# HAE_Sensors.net
KiCad netlist of a schematic drawn in Altium Designer
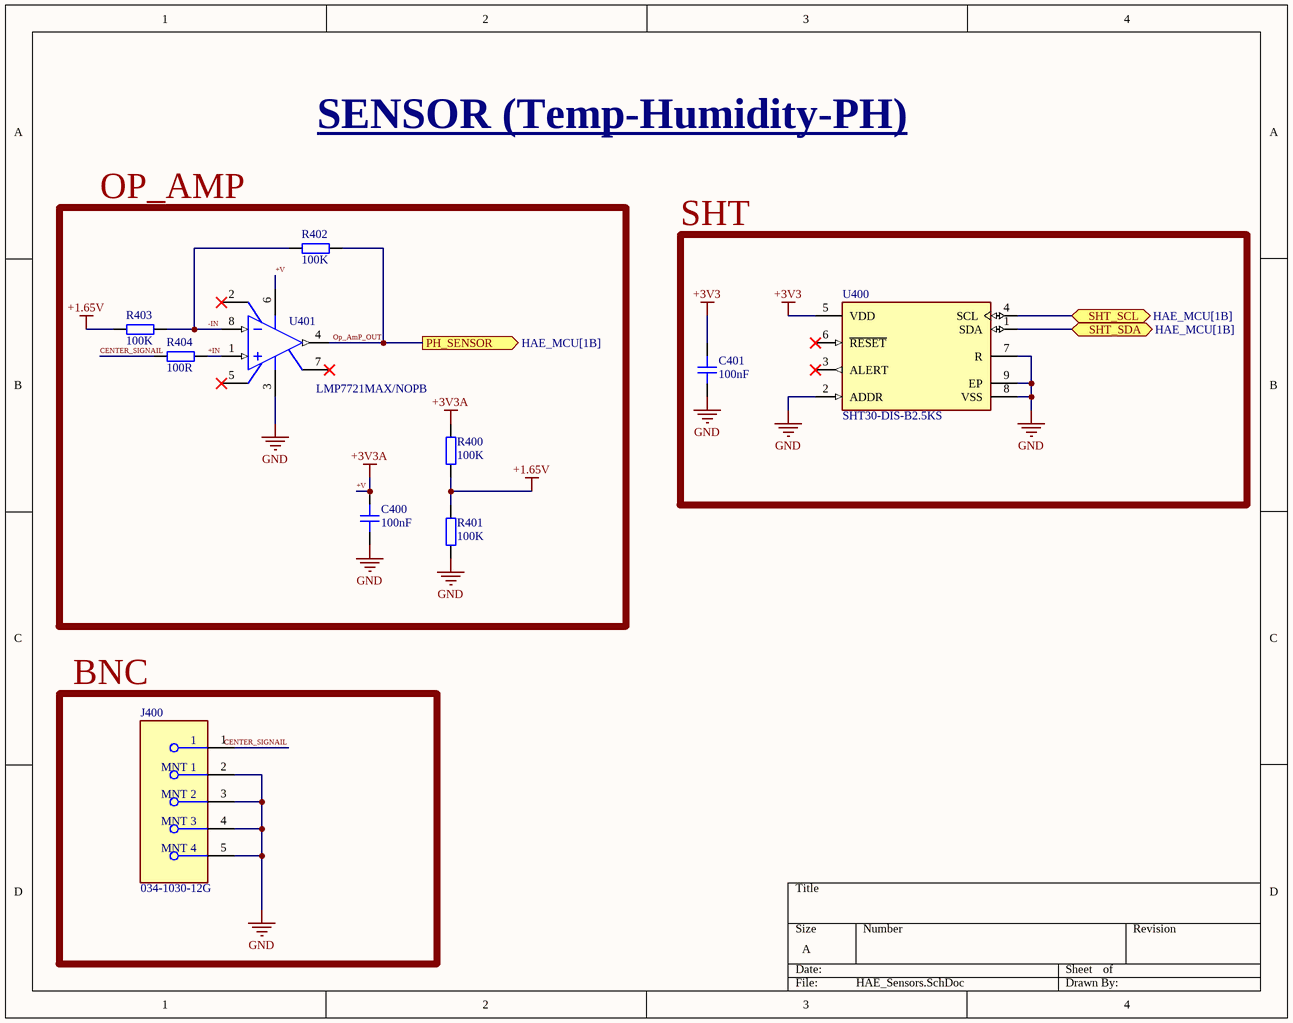
[diagram p0: HAE_Sensors.SchDoc]

(export (version "E")
  (design (tool "Eeschema 10.0.6"))
  (components
    (comp (ref "C400")
      (value "100nF")
      (footprint "CAP_0603")
      (description "Capacitor SMD 0603")
      (libsource (lib "PhilsLab_Library") (part "CAP_0603"))
    )
    (comp (ref "C401")
      (value "100nF")
      (footprint "CAP_0603")
      (description "Capacitor SMD 0603")
      (libsource (lib "PhilsLab_Library") (part "CAP_0603"))
    )
    (comp (ref "J400")
      (value "034-1030-12G")
      (footprint "FP-034-1030-12G-MFG")
      (description "CONN HDBNC JACK R/A 75 OHM PCB")
      (libsource (lib "Altium Content Vault") (part "9c40ac4d87bbbe9fcb330bd20f98ca3"))
    )
    (comp (ref "R400")
      (value "100K")
      (footprint "RES_0402")
      (description "Resistor SMD 0402")
      (libsource (lib "PhilsLab_Library") (part "RES_0402"))
    )
    (comp (ref "R401")
      (value "100K")
      (footprint "RES_0402")
      (description "Resistor SMD 0402")
      (libsource (lib "PhilsLab_Library") (part "RES_0402"))
    )
    (comp (ref "R402")
      (value "100K")
      (footprint "RES_0402")
      (description "Resistor SMD 0402")
      (libsource (lib "PhilsLab_Library") (part "RES_0402"))
    )
    (comp (ref "R403")
      (value "100K")
      (footprint "RES_0402")
      (description "Resistor SMD 0402")
      (libsource (lib "PhilsLab_Library") (part "RES_0402"))
    )
    (comp (ref "R404")
      (value "100R")
      (footprint "RES_0402")
      (description "Resistor SMD 0402")
      (libsource (lib "PhilsLab_Library") (part "RES_0402"))
    )
    (comp (ref "U400")
      (value "SHT30-DIS-B2.5KS")
      (footprint "FP-SHT30-DIS-B2_5KS-MFG")
      (description "SENSOR HUMID/TEMP 5V I2C 3% SMD")
      (libsource (lib "Altium Content Vault") (part "3a40f6fddac460f1c5fb2adec20f0f2"))
    )
    (comp (ref "U401")
      (value "LMP7721MAX/NOPB")
      (footprint "D0008A_L")
      (description "3 Femtoampere Input Bias Current Precision Amplifier, 8-pin Narrow SOIC, Pb-Free")
      (fields (field (name "MANUFACTURER") "Texas Instruments"))
      (libsource (lib "Altium Content Vault") (part "AMP-OPA-LMP7721-8"))
    )
  )
  (nets
    (net (code "1") (name "+1.65V") (class "Default")
      (node (ref "R400") (pin "2") (pinfunction "2_2") (pintype "passive"))
      (node (ref "R401") (pin "1") (pinfunction "1_1") (pintype "passive"))
      (node (ref "R403") (pin "1") (pinfunction "1_1") (pintype "passive"))
    )
    (net (code "2") (name "+3V3") (class "Default")
      (node (ref "C401") (pin "2") (pinfunction "2_2") (pintype "passive"))
      (node (ref "U400") (pin "5") (pinfunction "VDD_5") (pintype "power_in"))
    )
    (net (code "3") (name "+3V3A") (class "Default")
      (node (ref "C400") (pin "2") (pinfunction "2_2") (pintype "passive"))
      (node (ref "R400") (pin "1") (pinfunction "1_1") (pintype "passive"))
      (node (ref "U401") (pin "6") (pinfunction "V+_6") (pintype "power_in"))
    )
    (net (code "4") (name "/+IN") (class "Default")
      (node (ref "R404") (pin "1") (pinfunction "1_1") (pintype "passive"))
      (node (ref "U401") (pin "1") (pinfunction "IN+_1") (pintype "input"))
    )
    (net (code "5") (name "/-IN") (class "Default")
      (node (ref "R402") (pin "2") (pinfunction "2_2") (pintype "passive"))
      (node (ref "R403") (pin "2") (pinfunction "2_2") (pintype "passive"))
      (node (ref "U401") (pin "8") (pinfunction "IN-_8") (pintype "input"))
    )
    (net (code "6") (name "/CENTER_SIGNAIL") (class "Default")
      (node (ref "J400") (pin "1") (pinfunction "1_1") (pintype "passive"))
      (node (ref "R404") (pin "2") (pinfunction "2_2") (pintype "passive"))
    )
    (net (code "7") (name "/Op_AmP_OUT") (class "Default")
      (node (ref "R402") (pin "1") (pinfunction "1_1") (pintype "passive"))
      (node (ref "U401") (pin "4") (pinfunction "OUT_4") (pintype "output"))
    )
    (net (code "8") (name "/SHT_SCL") (class "Default")
      (node (ref "U400") (pin "4") (pinfunction "SCL_4") (pintype "bidirectional"))
    )
    (net (code "9") (name "/SHT_SDA") (class "Default")
      (node (ref "U400") (pin "1") (pinfunction "SDA_1") (pintype "bidirectional"))
    )
    (net (code "10") (name "GND") (class "Default")
      (node (ref "C400") (pin "1") (pinfunction "1_1") (pintype "passive"))
      (node (ref "C401") (pin "1") (pinfunction "1_1") (pintype "passive"))
      (node (ref "J400") (pin "2") (pinfunction "MNT_1_2") (pintype "passive"))
      (node (ref "J400") (pin "3") (pinfunction "MNT_2_3") (pintype "passive"))
      (node (ref "J400") (pin "4") (pinfunction "MNT_3_4") (pintype "passive"))
      (node (ref "J400") (pin "5") (pinfunction "MNT_4_5") (pintype "passive"))
      (node (ref "R401") (pin "2") (pinfunction "2_2") (pintype "passive"))
      (node (ref "U400") (pin "2") (pinfunction "ADDR_2") (pintype "input"))
      (node (ref "U400") (pin "7") (pinfunction "R_7") (pintype "passive"))
      (node (ref "U400") (pin "8") (pinfunction "VSS_8") (pintype "power_in"))
      (node (ref "U400") (pin "9") (pinfunction "EP_9") (pintype "passive"))
      (node (ref "U401") (pin "3") (pinfunction "V-_3") (pintype "power_in"))
    )
    (net (code "11") (name "unconnected-(U400-ALERT-Pad3)") (class "Default")
      (node (ref "U400") (pin "3") (pinfunction "ALERT_3") (pintype "output+no_connect"))
    )
    (net (code "12") (name "unconnected-(U400-~{RESET}-Pad6)") (class "Default")
      (node (ref "U400") (pin "6") (pinfunction "~{RESET}_6") (pintype "input+no_connect"))
    )
    (net (code "13") (name "unconnected-(U401-NC-Pad2)") (class "Default")
      (node (ref "U401") (pin "2") (pinfunction "NC_2") (pintype "passive+no_connect"))
    )
    (net (code "14") (name "unconnected-(U401-NC-Pad5)") (class "Default")
      (node (ref "U401") (pin "5") (pinfunction "NC_5") (pintype "passive+no_connect"))
    )
    (net (code "15") (name "unconnected-(U401-NC-Pad7)") (class "Default")
      (node (ref "U401") (pin "7") (pinfunction "NC_7") (pintype "passive+no_connect"))
    )
  )
)
